# SmartSwitch_i2c_mux.net
KiCad netlist of a schematic drawn in EAGLE
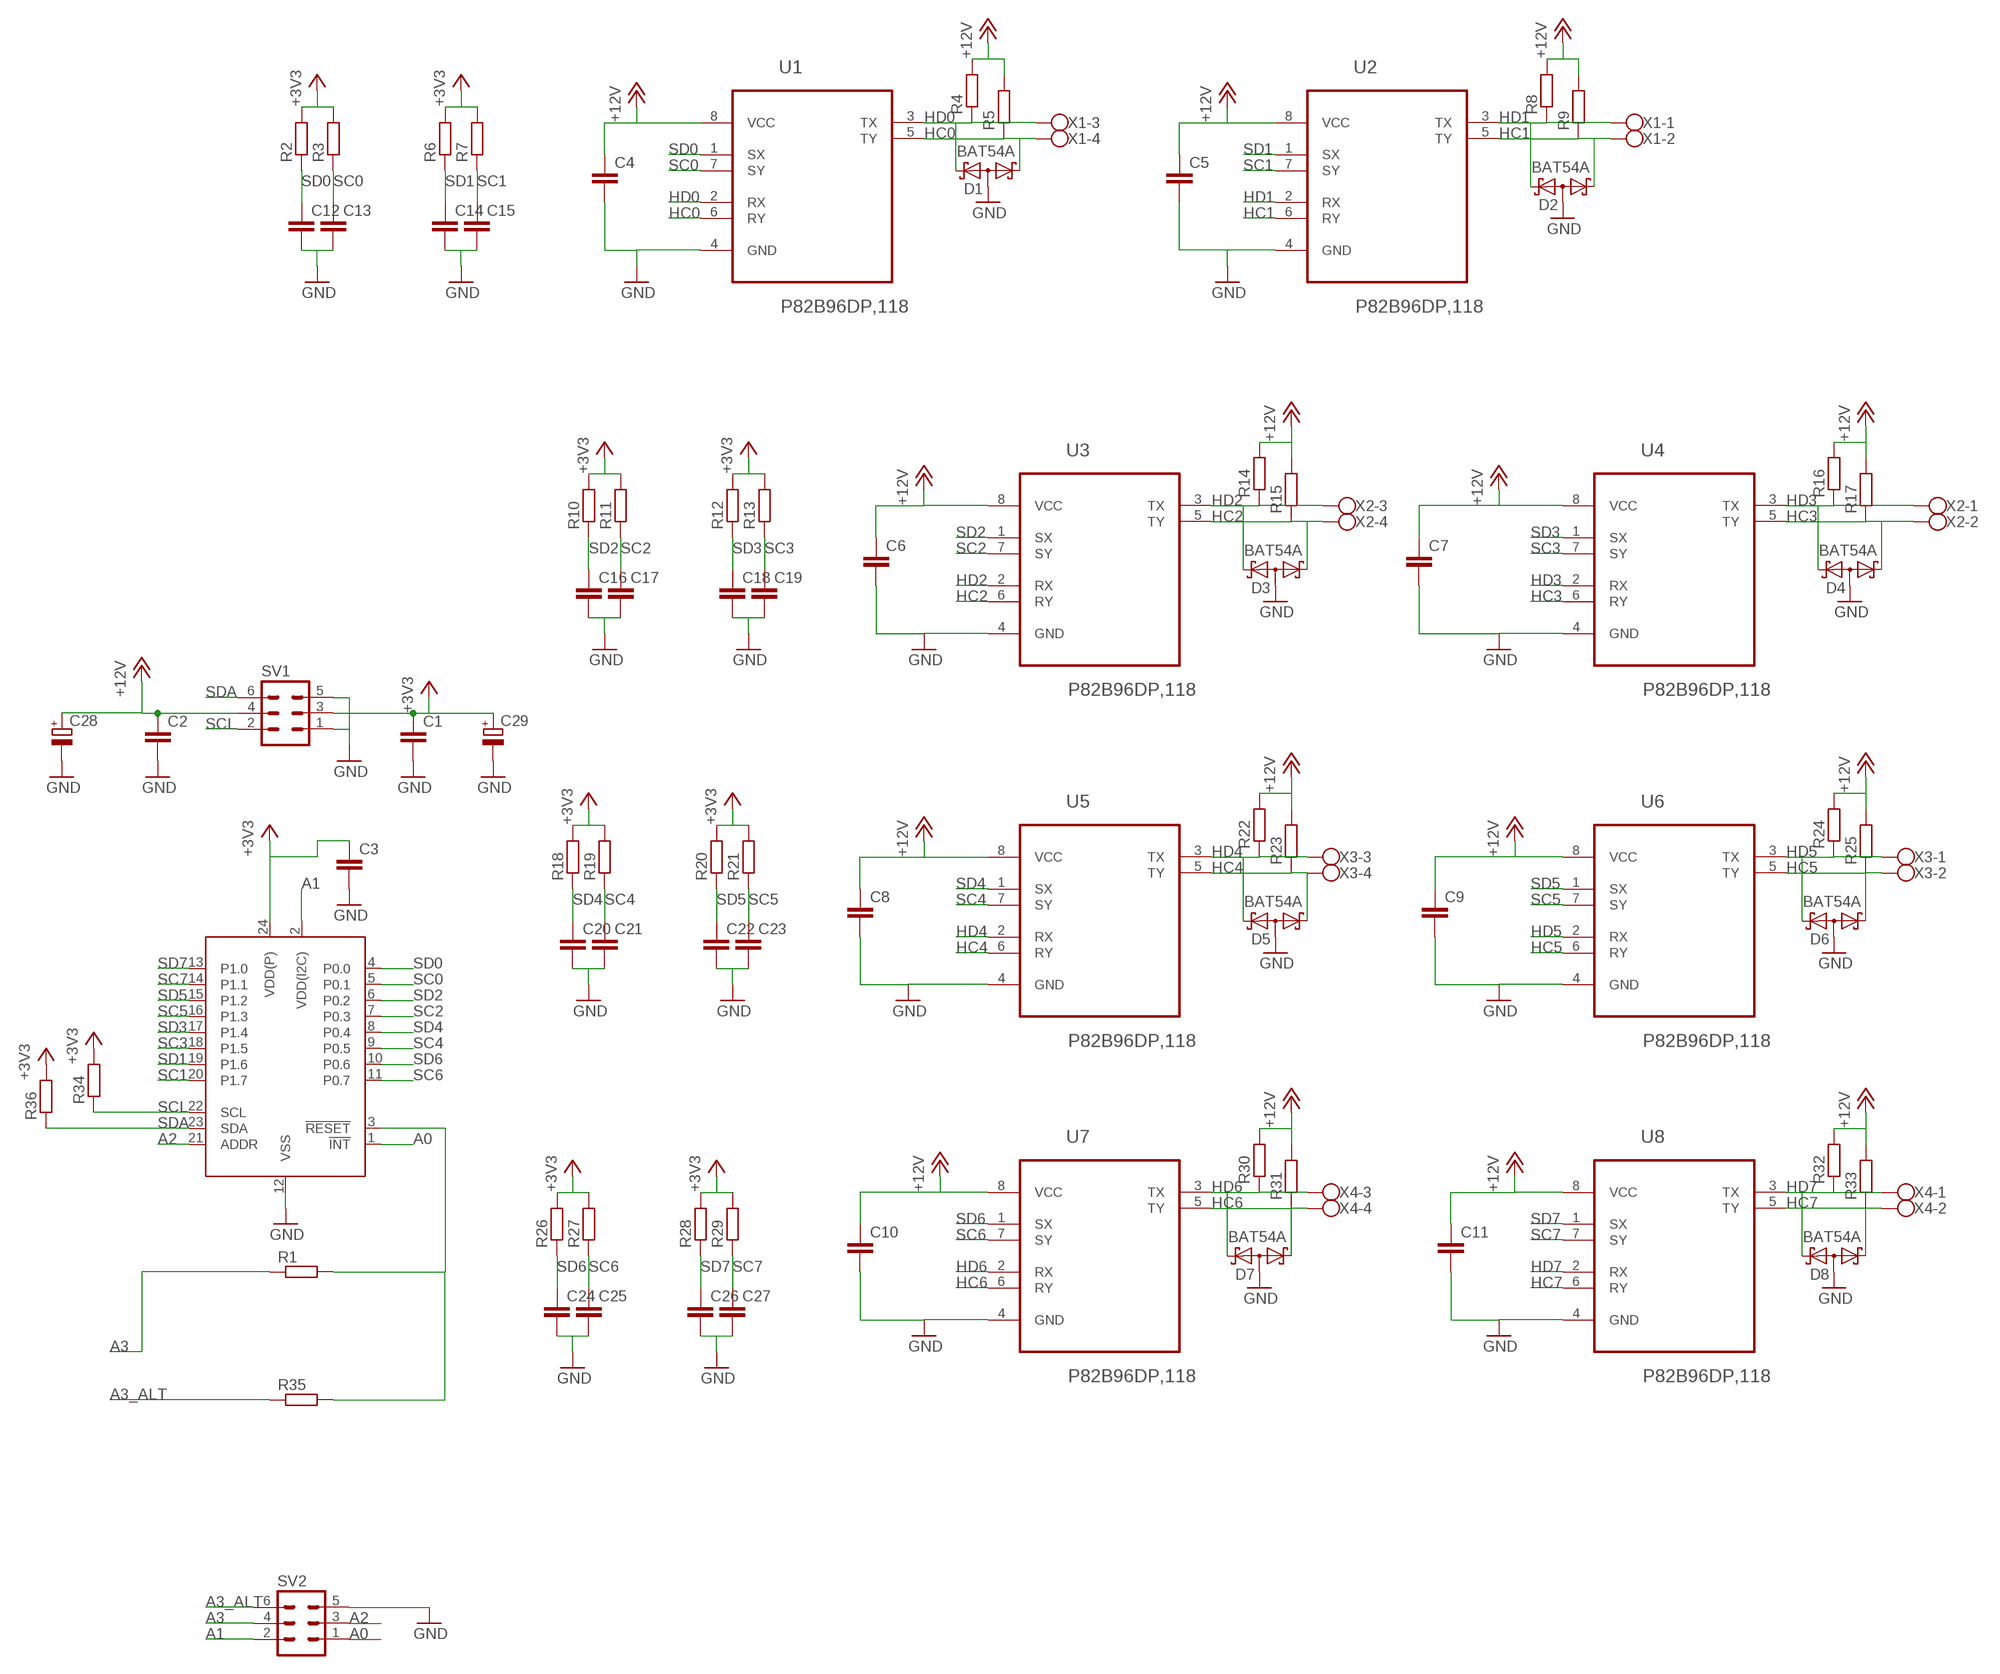
[diagram p0: schematic, sheet 1]

(export (version "E")
  (design (tool "Eeschema 10.0.6"))
  (components
    (comp (ref "C1")
      (value "C-EUC0805K")
      (footprint "eagle-import:C0805K")
      (libsource (lib "eagle-import") (part "C-EUC0805K"))
    )
    (comp (ref "C2")
      (value "C-EUC0805K")
      (footprint "eagle-import:C0805K")
      (libsource (lib "eagle-import") (part "C-EUC0805K"))
    )
    (comp (ref "C3")
      (value "C-EUC0603K")
      (footprint "eagle-import:C0603K")
      (libsource (lib "eagle-import") (part "C-EUC0603K"))
    )
    (comp (ref "C4")
      (value "C-EUC0603K")
      (footprint "eagle-import:C0603K")
      (libsource (lib "eagle-import") (part "C-EUC0603K"))
    )
    (comp (ref "C5")
      (value "C-EUC0603K")
      (footprint "eagle-import:C0603K")
      (libsource (lib "eagle-import") (part "C-EUC0603K"))
    )
    (comp (ref "C6")
      (value "C-EUC0603K")
      (footprint "eagle-import:C0603K")
      (libsource (lib "eagle-import") (part "C-EUC0603K"))
    )
    (comp (ref "C7")
      (value "C-EUC0603K")
      (footprint "eagle-import:C0603K")
      (libsource (lib "eagle-import") (part "C-EUC0603K"))
    )
    (comp (ref "C8")
      (value "C-EUC0603K")
      (footprint "eagle-import:C0603K")
      (libsource (lib "eagle-import") (part "C-EUC0603K"))
    )
    (comp (ref "C9")
      (value "C-EUC0603K")
      (footprint "eagle-import:C0603K")
      (libsource (lib "eagle-import") (part "C-EUC0603K"))
    )
    (comp (ref "C10")
      (value "C-EUC0603K")
      (footprint "eagle-import:C0603K")
      (libsource (lib "eagle-import") (part "C-EUC0603K"))
    )
    (comp (ref "C11")
      (value "C-EUC0603K")
      (footprint "eagle-import:C0603K")
      (libsource (lib "eagle-import") (part "C-EUC0603K"))
    )
    (comp (ref "C12")
      (value "C-EUC0402")
      (footprint "eagle-import:C0402")
      (libsource (lib "eagle-import") (part "C-EUC0402"))
    )
    (comp (ref "C13")
      (value "C-EUC0402")
      (footprint "eagle-import:C0402")
      (libsource (lib "eagle-import") (part "C-EUC0402"))
    )
    (comp (ref "C14")
      (value "C-EUC0402")
      (footprint "eagle-import:C0402")
      (libsource (lib "eagle-import") (part "C-EUC0402"))
    )
    (comp (ref "C15")
      (value "C-EUC0402")
      (footprint "eagle-import:C0402")
      (libsource (lib "eagle-import") (part "C-EUC0402"))
    )
    (comp (ref "C16")
      (value "C-EUC0402")
      (footprint "eagle-import:C0402")
      (libsource (lib "eagle-import") (part "C-EUC0402"))
    )
    (comp (ref "C17")
      (value "C-EUC0402")
      (footprint "eagle-import:C0402")
      (libsource (lib "eagle-import") (part "C-EUC0402"))
    )
    (comp (ref "C18")
      (value "C-EUC0402")
      (footprint "eagle-import:C0402")
      (libsource (lib "eagle-import") (part "C-EUC0402"))
    )
    (comp (ref "C19")
      (value "C-EUC0402")
      (footprint "eagle-import:C0402")
      (libsource (lib "eagle-import") (part "C-EUC0402"))
    )
    (comp (ref "C20")
      (value "C-EUC0402")
      (footprint "eagle-import:C0402")
      (libsource (lib "eagle-import") (part "C-EUC0402"))
    )
    (comp (ref "C21")
      (value "C-EUC0402")
      (footprint "eagle-import:C0402")
      (libsource (lib "eagle-import") (part "C-EUC0402"))
    )
    (comp (ref "C22")
      (value "C-EUC0402")
      (footprint "eagle-import:C0402")
      (libsource (lib "eagle-import") (part "C-EUC0402"))
    )
    (comp (ref "C23")
      (value "C-EUC0402")
      (footprint "eagle-import:C0402")
      (libsource (lib "eagle-import") (part "C-EUC0402"))
    )
    (comp (ref "C24")
      (value "C-EUC0402")
      (footprint "eagle-import:C0402")
      (libsource (lib "eagle-import") (part "C-EUC0402"))
    )
    (comp (ref "C25")
      (value "C-EUC0402")
      (footprint "eagle-import:C0402")
      (libsource (lib "eagle-import") (part "C-EUC0402"))
    )
    (comp (ref "C26")
      (value "C-EUC0402")
      (footprint "eagle-import:C0402")
      (libsource (lib "eagle-import") (part "C-EUC0402"))
    )
    (comp (ref "C27")
      (value "C-EUC0402")
      (footprint "eagle-import:C0402")
      (libsource (lib "eagle-import") (part "C-EUC0402"))
    )
    (comp (ref "C28")
      (value "CPOL-EUUD-6,3X7,7")
      (footprint "eagle-import:UD-6,3X7,7_NICHICON")
      (libsource (lib "eagle-import") (part "CPOL-EUUD-6,3X7,7"))
    )
    (comp (ref "C29")
      (value "CPOL-EUUD-6,3X7,7")
      (footprint "eagle-import:UD-6,3X7,7_NICHICON")
      (libsource (lib "eagle-import") (part "CPOL-EUUD-6,3X7,7"))
    )
    (comp (ref "D1")
      (value "BAT54A")
      (footprint "eagle-import:SOT23")
      (libsource (lib "eagle-import") (part "BAT54A"))
    )
    (comp (ref "D2")
      (value "BAT54A")
      (footprint "eagle-import:SOT23")
      (libsource (lib "eagle-import") (part "BAT54A"))
    )
    (comp (ref "D3")
      (value "BAT54A")
      (footprint "eagle-import:SOT23")
      (libsource (lib "eagle-import") (part "BAT54A"))
    )
    (comp (ref "D4")
      (value "BAT54A")
      (footprint "eagle-import:SOT23")
      (libsource (lib "eagle-import") (part "BAT54A"))
    )
    (comp (ref "D5")
      (value "BAT54A")
      (footprint "eagle-import:SOT23")
      (libsource (lib "eagle-import") (part "BAT54A"))
    )
    (comp (ref "D6")
      (value "BAT54A")
      (footprint "eagle-import:SOT23")
      (libsource (lib "eagle-import") (part "BAT54A"))
    )
    (comp (ref "D7")
      (value "BAT54A")
      (footprint "eagle-import:SOT23")
      (libsource (lib "eagle-import") (part "BAT54A"))
    )
    (comp (ref "D8")
      (value "BAT54A")
      (footprint "eagle-import:SOT23")
      (libsource (lib "eagle-import") (part "BAT54A"))
    )
    (comp (ref "R1")
      (value "R-EU_R0402")
      (footprint "eagle-import:R0402")
      (libsource (lib "eagle-import") (part "R-EU_R0402"))
    )
    (comp (ref "R2")
      (value "R-EU_R0603")
      (footprint "eagle-import:R0603")
      (libsource (lib "eagle-import") (part "R-EU_R0603"))
    )
    (comp (ref "R3")
      (value "R-EU_R0603")
      (footprint "eagle-import:R0603")
      (libsource (lib "eagle-import") (part "R-EU_R0603"))
    )
    (comp (ref "R4")
      (value "R-EU_R1206")
      (footprint "eagle-import:R1206")
      (libsource (lib "eagle-import") (part "R-EU_R1206"))
    )
    (comp (ref "R5")
      (value "R-EU_R1206")
      (footprint "eagle-import:R1206")
      (libsource (lib "eagle-import") (part "R-EU_R1206"))
    )
    (comp (ref "R6")
      (value "R-EU_R0603")
      (footprint "eagle-import:R0603")
      (libsource (lib "eagle-import") (part "R-EU_R0603"))
    )
    (comp (ref "R7")
      (value "R-EU_R0603")
      (footprint "eagle-import:R0603")
      (libsource (lib "eagle-import") (part "R-EU_R0603"))
    )
    (comp (ref "R8")
      (value "R-EU_R1206")
      (footprint "eagle-import:R1206")
      (libsource (lib "eagle-import") (part "R-EU_R1206"))
    )
    (comp (ref "R9")
      (value "R-EU_R1206")
      (footprint "eagle-import:R1206")
      (libsource (lib "eagle-import") (part "R-EU_R1206"))
    )
    (comp (ref "R10")
      (value "R-EU_R0603")
      (footprint "eagle-import:R0603")
      (libsource (lib "eagle-import") (part "R-EU_R0603"))
    )
    (comp (ref "R11")
      (value "R-EU_R0603")
      (footprint "eagle-import:R0603")
      (libsource (lib "eagle-import") (part "R-EU_R0603"))
    )
    (comp (ref "R12")
      (value "R-EU_R0603")
      (footprint "eagle-import:R0603")
      (libsource (lib "eagle-import") (part "R-EU_R0603"))
    )
    (comp (ref "R13")
      (value "R-EU_R0603")
      (footprint "eagle-import:R0603")
      (libsource (lib "eagle-import") (part "R-EU_R0603"))
    )
    (comp (ref "R14")
      (value "R-EU_R1206")
      (footprint "eagle-import:R1206")
      (libsource (lib "eagle-import") (part "R-EU_R1206"))
    )
    (comp (ref "R15")
      (value "R-EU_R1206")
      (footprint "eagle-import:R1206")
      (libsource (lib "eagle-import") (part "R-EU_R1206"))
    )
    (comp (ref "R16")
      (value "R-EU_R1206")
      (footprint "eagle-import:R1206")
      (libsource (lib "eagle-import") (part "R-EU_R1206"))
    )
    (comp (ref "R17")
      (value "R-EU_R1206")
      (footprint "eagle-import:R1206")
      (libsource (lib "eagle-import") (part "R-EU_R1206"))
    )
    (comp (ref "R18")
      (value "R-EU_R0603")
      (footprint "eagle-import:R0603")
      (libsource (lib "eagle-import") (part "R-EU_R0603"))
    )
    (comp (ref "R19")
      (value "R-EU_R0603")
      (footprint "eagle-import:R0603")
      (libsource (lib "eagle-import") (part "R-EU_R0603"))
    )
    (comp (ref "R20")
      (value "R-EU_R0603")
      (footprint "eagle-import:R0603")
      (libsource (lib "eagle-import") (part "R-EU_R0603"))
    )
    (comp (ref "R21")
      (value "R-EU_R0603")
      (footprint "eagle-import:R0603")
      (libsource (lib "eagle-import") (part "R-EU_R0603"))
    )
    (comp (ref "R22")
      (value "R-EU_R1206")
      (footprint "eagle-import:R1206")
      (libsource (lib "eagle-import") (part "R-EU_R1206"))
    )
    (comp (ref "R23")
      (value "R-EU_R1206")
      (footprint "eagle-import:R1206")
      (libsource (lib "eagle-import") (part "R-EU_R1206"))
    )
    (comp (ref "R24")
      (value "R-EU_R1206")
      (footprint "eagle-import:R1206")
      (libsource (lib "eagle-import") (part "R-EU_R1206"))
    )
    (comp (ref "R25")
      (value "R-EU_R1206")
      (footprint "eagle-import:R1206")
      (libsource (lib "eagle-import") (part "R-EU_R1206"))
    )
    (comp (ref "R26")
      (value "R-EU_R0603")
      (footprint "eagle-import:R0603")
      (libsource (lib "eagle-import") (part "R-EU_R0603"))
    )
    (comp (ref "R27")
      (value "R-EU_R0603")
      (footprint "eagle-import:R0603")
      (libsource (lib "eagle-import") (part "R-EU_R0603"))
    )
    (comp (ref "R28")
      (value "R-EU_R0603")
      (footprint "eagle-import:R0603")
      (libsource (lib "eagle-import") (part "R-EU_R0603"))
    )
    (comp (ref "R29")
      (value "R-EU_R0603")
      (footprint "eagle-import:R0603")
      (libsource (lib "eagle-import") (part "R-EU_R0603"))
    )
    (comp (ref "R30")
      (value "R-EU_R1206")
      (footprint "eagle-import:R1206")
      (libsource (lib "eagle-import") (part "R-EU_R1206"))
    )
    (comp (ref "R31")
      (value "R-EU_R1206")
      (footprint "eagle-import:R1206")
      (libsource (lib "eagle-import") (part "R-EU_R1206"))
    )
    (comp (ref "R32")
      (value "R-EU_R1206")
      (footprint "eagle-import:R1206")
      (libsource (lib "eagle-import") (part "R-EU_R1206"))
    )
    (comp (ref "R33")
      (value "R-EU_R1206")
      (footprint "eagle-import:R1206")
      (libsource (lib "eagle-import") (part "R-EU_R1206"))
    )
    (comp (ref "R34")
      (value "R-EU_R0603")
      (footprint "eagle-import:R0603")
      (libsource (lib "eagle-import") (part "R-EU_R0603"))
    )
    (comp (ref "R35")
      (value "R-EU_R0402")
      (footprint "eagle-import:R0402")
      (libsource (lib "eagle-import") (part "R-EU_R0402"))
    )
    (comp (ref "R36")
      (value "R-EU_R0603")
      (footprint "eagle-import:R0603")
      (libsource (lib "eagle-import") (part "R-EU_R0603"))
    )
    (comp (ref "SV1")
      (value "MA03-2")
      (footprint "eagle-import:MA03-2")
      (libsource (lib "eagle-import") (part "MA03-2"))
    )
    (comp (ref "SV2")
      (value "MA03-2")
      (footprint "eagle-import:MA03-2")
      (libsource (lib "eagle-import") (part "MA03-2"))
    )
    (comp (ref "U1")
      (value "P82B96DP,118")
      (footprint "eagle-import:SOP65P490X110-8N")
      (libsource (lib "eagle-import") (part "P82B96DP,118"))
    )
    (comp (ref "U2")
      (value "P82B96DP,118")
      (footprint "eagle-import:SOP65P490X110-8N")
      (libsource (lib "eagle-import") (part "P82B96DP,118"))
    )
    (comp (ref "U3")
      (value "P82B96DP,118")
      (footprint "eagle-import:SOP65P490X110-8N")
      (libsource (lib "eagle-import") (part "P82B96DP,118"))
    )
    (comp (ref "U4")
      (value "P82B96DP,118")
      (footprint "eagle-import:SOP65P490X110-8N")
      (libsource (lib "eagle-import") (part "P82B96DP,118"))
    )
    (comp (ref "U5")
      (value "P82B96DP,118")
      (footprint "eagle-import:SOP65P490X110-8N")
      (libsource (lib "eagle-import") (part "P82B96DP,118"))
    )
    (comp (ref "U6")
      (value "P82B96DP,118")
      (footprint "eagle-import:SOP65P490X110-8N")
      (libsource (lib "eagle-import") (part "P82B96DP,118"))
    )
    (comp (ref "U7")
      (value "P82B96DP,118")
      (footprint "eagle-import:SOP65P490X110-8N")
      (libsource (lib "eagle-import") (part "P82B96DP,118"))
    )
    (comp (ref "U8")
      (value "P82B96DP,118")
      (footprint "eagle-import:SOP65P490X110-8N")
      (libsource (lib "eagle-import") (part "P82B96DP,118"))
    )
    (comp (ref "U10")
      (value "PCAL6416APW")
      (footprint "eagle-import:SOT355-1")
      (libsource (lib "eagle-import") (part "PCAL6416APW"))
    )
    (comp (ref "X1")
      (value "W237-4")
      (footprint "eagle-import:W237-4")
      (libsource (lib "eagle-import") (part "W237-4"))
    )
    (comp (ref "X2")
      (value "W237-4")
      (footprint "eagle-import:W237-4")
      (libsource (lib "eagle-import") (part "W237-4"))
    )
    (comp (ref "X3")
      (value "W237-4")
      (footprint "eagle-import:W237-4")
      (libsource (lib "eagle-import") (part "W237-4"))
    )
    (comp (ref "X4")
      (value "W237-4")
      (footprint "eagle-import:W237-4")
      (libsource (lib "eagle-import") (part "W237-4"))
    )
  )
  (nets
    (net (code "1") (name "+3V3") (class "Default")
      (node (ref "C1") (pin "1") (pinfunction "1_1") (pintype "passive"))
      (node (ref "C29") (pin "+") (pinfunction "+_+") (pintype "passive"))
      (node (ref "C3") (pin "1") (pinfunction "1_1") (pintype "passive"))
      (node (ref "R10") (pin "2") (pinfunction "2_2") (pintype "passive"))
      (node (ref "R11") (pin "2") (pinfunction "2_2") (pintype "passive"))
      (node (ref "R12") (pin "2") (pinfunction "2_2") (pintype "passive"))
      (node (ref "R13") (pin "2") (pinfunction "2_2") (pintype "passive"))
      (node (ref "R18") (pin "2") (pinfunction "2_2") (pintype "passive"))
      (node (ref "R19") (pin "2") (pinfunction "2_2") (pintype "passive"))
      (node (ref "R2") (pin "2") (pinfunction "2_2") (pintype "passive"))
      (node (ref "R20") (pin "2") (pinfunction "2_2") (pintype "passive"))
      (node (ref "R21") (pin "2") (pinfunction "2_2") (pintype "passive"))
      (node (ref "R26") (pin "2") (pinfunction "2_2") (pintype "passive"))
      (node (ref "R27") (pin "2") (pinfunction "2_2") (pintype "passive"))
      (node (ref "R28") (pin "2") (pinfunction "2_2") (pintype "passive"))
      (node (ref "R29") (pin "2") (pinfunction "2_2") (pintype "passive"))
      (node (ref "R3") (pin "2") (pinfunction "2_2") (pintype "passive"))
      (node (ref "R34") (pin "2") (pinfunction "2_2") (pintype "passive"))
      (node (ref "R36") (pin "2") (pinfunction "2_2") (pintype "passive"))
      (node (ref "R6") (pin "2") (pinfunction "2_2") (pintype "passive"))
      (node (ref "R7") (pin "2") (pinfunction "2_2") (pintype "passive"))
      (node (ref "SV1") (pin "3") (pinfunction "3_3") (pintype "passive"))
      (node (ref "U10") (pin "24") (pinfunction "VDD(P)_24") (pintype "power_in"))
    )
    (net (code "2") (name "+12V") (class "Default")
      (node (ref "C10") (pin "1") (pinfunction "1_1") (pintype "passive"))
      (node (ref "C11") (pin "1") (pinfunction "1_1") (pintype "passive"))
      (node (ref "C2") (pin "1") (pinfunction "1_1") (pintype "passive"))
      (node (ref "C28") (pin "+") (pinfunction "+_+") (pintype "passive"))
      (node (ref "C4") (pin "1") (pinfunction "1_1") (pintype "passive"))
      (node (ref "C5") (pin "1") (pinfunction "1_1") (pintype "passive"))
      (node (ref "C6") (pin "1") (pinfunction "1_1") (pintype "passive"))
      (node (ref "C7") (pin "1") (pinfunction "1_1") (pintype "passive"))
      (node (ref "C8") (pin "1") (pinfunction "1_1") (pintype "passive"))
      (node (ref "C9") (pin "1") (pinfunction "1_1") (pintype "passive"))
      (node (ref "R14") (pin "2") (pinfunction "2_2") (pintype "passive"))
      (node (ref "R15") (pin "2") (pinfunction "2_2") (pintype "passive"))
      (node (ref "R16") (pin "2") (pinfunction "2_2") (pintype "passive"))
      (node (ref "R17") (pin "2") (pinfunction "2_2") (pintype "passive"))
      (node (ref "R22") (pin "2") (pinfunction "2_2") (pintype "passive"))
      (node (ref "R23") (pin "2") (pinfunction "2_2") (pintype "passive"))
      (node (ref "R24") (pin "2") (pinfunction "2_2") (pintype "passive"))
      (node (ref "R25") (pin "2") (pinfunction "2_2") (pintype "passive"))
      (node (ref "R30") (pin "2") (pinfunction "2_2") (pintype "passive"))
      (node (ref "R31") (pin "2") (pinfunction "2_2") (pintype "passive"))
      (node (ref "R32") (pin "2") (pinfunction "2_2") (pintype "passive"))
      (node (ref "R33") (pin "2") (pinfunction "2_2") (pintype "passive"))
      (node (ref "R4") (pin "2") (pinfunction "2_2") (pintype "passive"))
      (node (ref "R5") (pin "2") (pinfunction "2_2") (pintype "passive"))
      (node (ref "R8") (pin "2") (pinfunction "2_2") (pintype "passive"))
      (node (ref "R9") (pin "2") (pinfunction "2_2") (pintype "passive"))
      (node (ref "SV1") (pin "4") (pinfunction "4_4") (pintype "passive"))
      (node (ref "U1") (pin "8") (pinfunction "VCC_8") (pintype "power_in"))
      (node (ref "U2") (pin "8") (pinfunction "VCC_8") (pintype "power_in"))
      (node (ref "U3") (pin "8") (pinfunction "VCC_8") (pintype "power_in"))
      (node (ref "U4") (pin "8") (pinfunction "VCC_8") (pintype "power_in"))
      (node (ref "U5") (pin "8") (pinfunction "VCC_8") (pintype "power_in"))
      (node (ref "U6") (pin "8") (pinfunction "VCC_8") (pintype "power_in"))
      (node (ref "U7") (pin "8") (pinfunction "VCC_8") (pintype "power_in"))
      (node (ref "U8") (pin "8") (pinfunction "VCC_8") (pintype "power_in"))
    )
    (net (code "3") (name "/A0") (class "Default")
      (node (ref "SV2") (pin "1") (pinfunction "1_1") (pintype "passive"))
      (node (ref "U10") (pin "1") (pinfunction "~{INT}_1") (pintype "output"))
    )
    (net (code "4") (name "/A1") (class "Default")
      (node (ref "SV2") (pin "2") (pinfunction "2_2") (pintype "passive"))
      (node (ref "U10") (pin "2") (pinfunction "VDD(I2C)_2") (pintype "power_in"))
    )
    (net (code "5") (name "/A2") (class "Default")
      (node (ref "SV2") (pin "3") (pinfunction "3_3") (pintype "passive"))
      (node (ref "U10") (pin "21") (pinfunction "ADDR_21") (pintype "input"))
    )
    (net (code "6") (name "/A3") (class "Default")
      (node (ref "R1") (pin "1") (pinfunction "1_1") (pintype "passive"))
      (node (ref "SV2") (pin "4") (pinfunction "4_4") (pintype "passive"))
    )
    (net (code "7") (name "/A3_ALT") (class "Default")
      (node (ref "R35") (pin "1") (pinfunction "1_1") (pintype "passive"))
      (node (ref "SV2") (pin "6") (pinfunction "6_6") (pintype "passive"))
    )
    (net (code "8") (name "/HC0") (class "Default")
      (node (ref "D1") (pin "1") (pinfunction "K1_1") (pintype "passive"))
      (node (ref "R5") (pin "1") (pinfunction "1_1") (pintype "passive"))
      (node (ref "U1") (pin "5") (pinfunction "TY_5") (pintype "output"))
      (node (ref "U1") (pin "6") (pinfunction "RY_6") (pintype "input"))
      (node (ref "X1") (pin "4") (pinfunction "KL_4") (pintype "passive"))
    )
    (net (code "9") (name "/HC1") (class "Default")
      (node (ref "D2") (pin "1") (pinfunction "K1_1") (pintype "passive"))
      (node (ref "R9") (pin "1") (pinfunction "1_1") (pintype "passive"))
      (node (ref "U2") (pin "5") (pinfunction "TY_5") (pintype "output"))
      (node (ref "U2") (pin "6") (pinfunction "RY_6") (pintype "input"))
      (node (ref "X1") (pin "2") (pinfunction "KL_2") (pintype "passive"))
    )
    (net (code "10") (name "/HC2") (class "Default")
      (node (ref "D3") (pin "1") (pinfunction "K1_1") (pintype "passive"))
      (node (ref "R15") (pin "1") (pinfunction "1_1") (pintype "passive"))
      (node (ref "U3") (pin "5") (pinfunction "TY_5") (pintype "output"))
      (node (ref "U3") (pin "6") (pinfunction "RY_6") (pintype "input"))
      (node (ref "X2") (pin "4") (pinfunction "KL_4") (pintype "passive"))
    )
    (net (code "11") (name "/HC3") (class "Default")
      (node (ref "D4") (pin "1") (pinfunction "K1_1") (pintype "passive"))
      (node (ref "R17") (pin "1") (pinfunction "1_1") (pintype "passive"))
      (node (ref "U4") (pin "5") (pinfunction "TY_5") (pintype "output"))
      (node (ref "U4") (pin "6") (pinfunction "RY_6") (pintype "input"))
      (node (ref "X2") (pin "2") (pinfunction "KL_2") (pintype "passive"))
    )
    (net (code "12") (name "/HC4") (class "Default")
      (node (ref "D5") (pin "1") (pinfunction "K1_1") (pintype "passive"))
      (node (ref "R23") (pin "1") (pinfunction "1_1") (pintype "passive"))
      (node (ref "U5") (pin "5") (pinfunction "TY_5") (pintype "output"))
      (node (ref "U5") (pin "6") (pinfunction "RY_6") (pintype "input"))
      (node (ref "X3") (pin "4") (pinfunction "KL_4") (pintype "passive"))
    )
    (net (code "13") (name "/HC5") (class "Default")
      (node (ref "D6") (pin "1") (pinfunction "K1_1") (pintype "passive"))
      (node (ref "R25") (pin "1") (pinfunction "1_1") (pintype "passive"))
      (node (ref "U6") (pin "5") (pinfunction "TY_5") (pintype "output"))
      (node (ref "U6") (pin "6") (pinfunction "RY_6") (pintype "input"))
      (node (ref "X3") (pin "2") (pinfunction "KL_2") (pintype "passive"))
    )
    (net (code "14") (name "/HC6") (class "Default")
      (node (ref "D7") (pin "1") (pinfunction "K1_1") (pintype "passive"))
      (node (ref "R31") (pin "1") (pinfunction "1_1") (pintype "passive"))
      (node (ref "U7") (pin "5") (pinfunction "TY_5") (pintype "output"))
      (node (ref "U7") (pin "6") (pinfunction "RY_6") (pintype "input"))
      (node (ref "X4") (pin "4") (pinfunction "KL_4") (pintype "passive"))
    )
    (net (code "15") (name "/HC7") (class "Default")
      (node (ref "D8") (pin "1") (pinfunction "K1_1") (pintype "passive"))
      (node (ref "R33") (pin "1") (pinfunction "1_1") (pintype "passive"))
      (node (ref "U8") (pin "5") (pinfunction "TY_5") (pintype "output"))
      (node (ref "U8") (pin "6") (pinfunction "RY_6") (pintype "input"))
      (node (ref "X4") (pin "2") (pinfunction "KL_2") (pintype "passive"))
    )
    (net (code "16") (name "/HD0") (class "Default")
      (node (ref "D1") (pin "2") (pinfunction "K2_2") (pintype "passive"))
      (node (ref "R4") (pin "1") (pinfunction "1_1") (pintype "passive"))
      (node (ref "U1") (pin "2") (pinfunction "RX_2") (pintype "input"))
      (node (ref "U1") (pin "3") (pinfunction "TX_3") (pintype "output"))
      (node (ref "X1") (pin "3") (pinfunction "KL_3") (pintype "passive"))
    )
    (net (code "17") (name "/HD1") (class "Default")
      (node (ref "D2") (pin "2") (pinfunction "K2_2") (pintype "passive"))
      (node (ref "R8") (pin "1") (pinfunction "1_1") (pintype "passive"))
      (node (ref "U2") (pin "2") (pinfunction "RX_2") (pintype "input"))
      (node (ref "U2") (pin "3") (pinfunction "TX_3") (pintype "output"))
      (node (ref "X1") (pin "1") (pinfunction "KL_1") (pintype "passive"))
    )
    (net (code "18") (name "/HD2") (class "Default")
      (node (ref "D3") (pin "2") (pinfunction "K2_2") (pintype "passive"))
      (node (ref "R14") (pin "1") (pinfunction "1_1") (pintype "passive"))
      (node (ref "U3") (pin "2") (pinfunction "RX_2") (pintype "input"))
      (node (ref "U3") (pin "3") (pinfunction "TX_3") (pintype "output"))
      (node (ref "X2") (pin "3") (pinfunction "KL_3") (pintype "passive"))
    )
    (net (code "19") (name "/HD3") (class "Default")
      (node (ref "D4") (pin "2") (pinfunction "K2_2") (pintype "passive"))
      (node (ref "R16") (pin "1") (pinfunction "1_1") (pintype "passive"))
      (node (ref "U4") (pin "2") (pinfunction "RX_2") (pintype "input"))
      (node (ref "U4") (pin "3") (pinfunction "TX_3") (pintype "output"))
      (node (ref "X2") (pin "1") (pinfunction "KL_1") (pintype "passive"))
    )
    (net (code "20") (name "/HD4") (class "Default")
      (node (ref "D5") (pin "2") (pinfunction "K2_2") (pintype "passive"))
      (node (ref "R22") (pin "1") (pinfunction "1_1") (pintype "passive"))
      (node (ref "U5") (pin "2") (pinfunction "RX_2") (pintype "input"))
      (node (ref "U5") (pin "3") (pinfunction "TX_3") (pintype "output"))
      (node (ref "X3") (pin "3") (pinfunction "KL_3") (pintype "passive"))
    )
    (net (code "21") (name "/HD5") (class "Default")
      (node (ref "D6") (pin "2") (pinfunction "K2_2") (pintype "passive"))
      (node (ref "R24") (pin "1") (pinfunction "1_1") (pintype "passive"))
      (node (ref "U6") (pin "2") (pinfunction "RX_2") (pintype "input"))
      (node (ref "U6") (pin "3") (pinfunction "TX_3") (pintype "output"))
      (node (ref "X3") (pin "1") (pinfunction "KL_1") (pintype "passive"))
    )
    (net (code "22") (name "/HD6") (class "Default")
      (node (ref "D7") (pin "2") (pinfunction "K2_2") (pintype "passive"))
      (node (ref "R30") (pin "1") (pinfunction "1_1") (pintype "passive"))
      (node (ref "U7") (pin "2") (pinfunction "RX_2") (pintype "input"))
      (node (ref "U7") (pin "3") (pinfunction "TX_3") (pintype "output"))
      (node (ref "X4") (pin "3") (pinfunction "KL_3") (pintype "passive"))
    )
    (net (code "23") (name "/HD7") (class "Default")
      (node (ref "D8") (pin "2") (pinfunction "K2_2") (pintype "passive"))
      (node (ref "R32") (pin "1") (pinfunction "1_1") (pintype "passive"))
      (node (ref "U8") (pin "2") (pinfunction "RX_2") (pintype "input"))
      (node (ref "U8") (pin "3") (pinfunction "TX_3") (pintype "output"))
      (node (ref "X4") (pin "1") (pinfunction "KL_1") (pintype "passive"))
    )
    (net (code "24") (name "/SC0") (class "Default")
      (node (ref "C13") (pin "1") (pinfunction "1_1") (pintype "passive"))
      (node (ref "R3") (pin "1") (pinfunction "1_1") (pintype "passive"))
      (node (ref "U1") (pin "7") (pinfunction "SY_7") (pintype "bidirectional"))
      (node (ref "U10") (pin "5") (pinfunction "P0.1_5") (pintype "bidirectional"))
    )
    (net (code "25") (name "/SC1") (class "Default")
      (node (ref "C15") (pin "1") (pinfunction "1_1") (pintype "passive"))
      (node (ref "R7") (pin "1") (pinfunction "1_1") (pintype "passive"))
      (node (ref "U10") (pin "20") (pinfunction "P1.7_20") (pintype "bidirectional"))
      (node (ref "U2") (pin "7") (pinfunction "SY_7") (pintype "bidirectional"))
    )
    (net (code "26") (name "/SC2") (class "Default")
      (node (ref "C17") (pin "1") (pinfunction "1_1") (pintype "passive"))
      (node (ref "R11") (pin "1") (pinfunction "1_1") (pintype "passive"))
      (node (ref "U10") (pin "7") (pinfunction "P0.3_7") (pintype "bidirectional"))
      (node (ref "U3") (pin "7") (pinfunction "SY_7") (pintype "bidirectional"))
    )
    (net (code "27") (name "/SC3") (class "Default")
      (node (ref "C19") (pin "1") (pinfunction "1_1") (pintype "passive"))
      (node (ref "R13") (pin "1") (pinfunction "1_1") (pintype "passive"))
      (node (ref "U10") (pin "18") (pinfunction "P1.5_18") (pintype "bidirectional"))
      (node (ref "U4") (pin "7") (pinfunction "SY_7") (pintype "bidirectional"))
    )
    (net (code "28") (name "/SC4") (class "Default")
      (node (ref "C21") (pin "1") (pinfunction "1_1") (pintype "passive"))
      (node (ref "R19") (pin "1") (pinfunction "1_1") (pintype "passive"))
      (node (ref "U10") (pin "9") (pinfunction "P0.5_9") (pintype "bidirectional"))
      (node (ref "U5") (pin "7") (pinfunction "SY_7") (pintype "bidirectional"))
    )
    (net (code "29") (name "/SC5") (class "Default")
      (node (ref "C23") (pin "1") (pinfunction "1_1") (pintype "passive"))
      (node (ref "R21") (pin "1") (pinfunction "1_1") (pintype "passive"))
      (node (ref "U10") (pin "16") (pinfunction "P1.3_16") (pintype "bidirectional"))
      (node (ref "U6") (pin "7") (pinfunction "SY_7") (pintype "bidirectional"))
    )
    (net (code "30") (name "/SC6") (class "Default")
      (node (ref "C25") (pin "1") (pinfunction "1_1") (pintype "passive"))
      (node (ref "R27") (pin "1") (pinfunction "1_1") (pintype "passive"))
      (node (ref "U10") (pin "11") (pinfunction "P0.7_11") (pintype "bidirectional"))
      (node (ref "U7") (pin "7") (pinfunction "SY_7") (pintype "bidirectional"))
    )
    (net (code "31") (name "/SC7") (class "Default")
      (node (ref "C27") (pin "1") (pinfunction "1_1") (pintype "passive"))
      (node (ref "R29") (pin "1") (pinfunction "1_1") (pintype "passive"))
      (node (ref "U10") (pin "14") (pinfunction "P1.1_14") (pintype "bidirectional"))
      (node (ref "U8") (pin "7") (pinfunction "SY_7") (pintype "bidirectional"))
    )
    (net (code "32") (name "/SCL") (class "Default")
      (node (ref "R34") (pin "1") (pinfunction "1_1") (pintype "passive"))
      (node (ref "SV1") (pin "2") (pinfunction "2_2") (pintype "passive"))
      (node (ref "U10") (pin "22") (pinfunction "SCL_22") (pintype "bidirectional"))
    )
    (net (code "33") (name "/SD0") (class "Default")
      (node (ref "C12") (pin "1") (pinfunction "1_1") (pintype "passive"))
      (node (ref "R2") (pin "1") (pinfunction "1_1") (pintype "passive"))
      (node (ref "U1") (pin "1") (pinfunction "SX_1") (pintype "bidirectional"))
      (node (ref "U10") (pin "4") (pinfunction "P0.0_4") (pintype "bidirectional"))
    )
    (net (code "34") (name "/SD1") (class "Default")
      (node (ref "C14") (pin "1") (pinfunction "1_1") (pintype "passive"))
      (node (ref "R6") (pin "1") (pinfunction "1_1") (pintype "passive"))
      (node (ref "U10") (pin "19") (pinfunction "P1.6_19") (pintype "bidirectional"))
      (node (ref "U2") (pin "1") (pinfunction "SX_1") (pintype "bidirectional"))
    )
    (net (code "35") (name "/SD2") (class "Default")
      (node (ref "C16") (pin "1") (pinfunction "1_1") (pintype "passive"))
      (node (ref "R10") (pin "1") (pinfunction "1_1") (pintype "passive"))
      (node (ref "U10") (pin "6") (pinfunction "P0.2_6") (pintype "bidirectional"))
      (node (ref "U3") (pin "1") (pinfunction "SX_1") (pintype "bidirectional"))
    )
    (net (code "36") (name "/SD3") (class "Default")
      (node (ref "C18") (pin "1") (pinfunction "1_1") (pintype "passive"))
      (node (ref "R12") (pin "1") (pinfunction "1_1") (pintype "passive"))
      (node (ref "U10") (pin "17") (pinfunction "P1.4_17") (pintype "bidirectional"))
      (node (ref "U4") (pin "1") (pinfunction "SX_1") (pintype "bidirectional"))
    )
    (net (code "37") (name "/SD4") (class "Default")
      (node (ref "C20") (pin "1") (pinfunction "1_1") (pintype "passive"))
      (node (ref "R18") (pin "1") (pinfunction "1_1") (pintype "passive"))
      (node (ref "U10") (pin "8") (pinfunction "P0.4_8") (pintype "bidirectional"))
      (node (ref "U5") (pin "1") (pinfunction "SX_1") (pintype "bidirectional"))
    )
    (net (code "38") (name "/SD5") (class "Default")
      (node (ref "C22") (pin "1") (pinfunction "1_1") (pintype "passive"))
      (node (ref "R20") (pin "1") (pinfunction "1_1") (pintype "passive"))
      (node (ref "U10") (pin "15") (pinfunction "P1.2_15") (pintype "bidirectional"))
      (node (ref "U6") (pin "1") (pinfunction "SX_1") (pintype "bidirectional"))
    )
    (net (code "39") (name "/SD6") (class "Default")
      (node (ref "C24") (pin "1") (pinfunction "1_1") (pintype "passive"))
      (node (ref "R26") (pin "1") (pinfunction "1_1") (pintype "passive"))
      (node (ref "U10") (pin "10") (pinfunction "P0.6_10") (pintype "bidirectional"))
      (node (ref "U7") (pin "1") (pinfunction "SX_1") (pintype "bidirectional"))
    )
    (net (code "40") (name "/SD7") (class "Default")
      (node (ref "C26") (pin "1") (pinfunction "1_1") (pintype "passive"))
      (node (ref "R28") (pin "1") (pinfunction "1_1") (pintype "passive"))
      (node (ref "U10") (pin "13") (pinfunction "P1.0_13") (pintype "bidirectional"))
      (node (ref "U8") (pin "1") (pinfunction "SX_1") (pintype "bidirectional"))
    )
    (net (code "41") (name "/SDA") (class "Default")
      (node (ref "R36") (pin "1") (pinfunction "1_1") (pintype "passive"))
      (node (ref "SV1") (pin "6") (pinfunction "6_6") (pintype "passive"))
      (node (ref "U10") (pin "23") (pinfunction "SDA_23") (pintype "bidirectional"))
    )
    (net (code "42") (name "GND") (class "Default")
      (node (ref "C1") (pin "2") (pinfunction "2_2") (pintype "passive"))
      (node (ref "C10") (pin "2") (pinfunction "2_2") (pintype "passive"))
      (node (ref "C11") (pin "2") (pinfunction "2_2") (pintype "passive"))
      (node (ref "C12") (pin "2") (pinfunction "2_2") (pintype "passive"))
      (node (ref "C13") (pin "2") (pinfunction "2_2") (pintype "passive"))
      (node (ref "C14") (pin "2") (pinfunction "2_2") (pintype "passive"))
      (node (ref "C15") (pin "2") (pinfunction "2_2") (pintype "passive"))
      (node (ref "C16") (pin "2") (pinfunction "2_2") (pintype "passive"))
      (node (ref "C17") (pin "2") (pinfunction "2_2") (pintype "passive"))
      (node (ref "C18") (pin "2") (pinfunction "2_2") (pintype "passive"))
      (node (ref "C19") (pin "2") (pinfunction "2_2") (pintype "passive"))
      (node (ref "C2") (pin "2") (pinfunction "2_2") (pintype "passive"))
      (node (ref "C20") (pin "2") (pinfunction "2_2") (pintype "passive"))
      (node (ref "C21") (pin "2") (pinfunction "2_2") (pintype "passive"))
      (node (ref "C22") (pin "2") (pinfunction "2_2") (pintype "passive"))
      (node (ref "C23") (pin "2") (pinfunction "2_2") (pintype "passive"))
      (node (ref "C24") (pin "2") (pinfunction "2_2") (pintype "passive"))
      (node (ref "C25") (pin "2") (pinfunction "2_2") (pintype "passive"))
      (node (ref "C26") (pin "2") (pinfunction "2_2") (pintype "passive"))
      (node (ref "C27") (pin "2") (pinfunction "2_2") (pintype "passive"))
      (node (ref "C28") (pin "-") (pinfunction "-_-") (pintype "passive"))
      (node (ref "C29") (pin "-") (pinfunction "-_-") (pintype "passive"))
      (node (ref "C3") (pin "2") (pinfunction "2_2") (pintype "passive"))
      (node (ref "C4") (pin "2") (pinfunction "2_2") (pintype "passive"))
      (node (ref "C5") (pin "2") (pinfunction "2_2") (pintype "passive"))
      (node (ref "C6") (pin "2") (pinfunction "2_2") (pintype "passive"))
      (node (ref "C7") (pin "2") (pinfunction "2_2") (pintype "passive"))
      (node (ref "C8") (pin "2") (pinfunction "2_2") (pintype "passive"))
      (node (ref "C9") (pin "2") (pinfunction "2_2") (pintype "passive"))
      (node (ref "D1") (pin "3") (pinfunction "A1A2_3") (pintype "passive"))
      (node (ref "D2") (pin "3") (pinfunction "A1A2_3") (pintype "passive"))
      (node (ref "D3") (pin "3") (pinfunction "A1A2_3") (pintype "passive"))
      (node (ref "D4") (pin "3") (pinfunction "A1A2_3") (pintype "passive"))
      (node (ref "D5") (pin "3") (pinfunction "A1A2_3") (pintype "passive"))
      (node (ref "D6") (pin "3") (pinfunction "A1A2_3") (pintype "passive"))
      (node (ref "D7") (pin "3") (pinfunction "A1A2_3") (pintype "passive"))
      (node (ref "D8") (pin "3") (pinfunction "A1A2_3") (pintype "passive"))
      (node (ref "SV1") (pin "1") (pinfunction "1_1") (pintype "passive"))
      (node (ref "SV1") (pin "5") (pinfunction "5_5") (pintype "passive"))
      (node (ref "SV2") (pin "5") (pinfunction "5_5") (pintype "passive"))
      (node (ref "U1") (pin "4") (pinfunction "GND_4") (pintype "passive"))
      (node (ref "U10") (pin "12") (pinfunction "VSS_12") (pintype "bidirectional"))
      (node (ref "U2") (pin "4") (pinfunction "GND_4") (pintype "passive"))
      (node (ref "U3") (pin "4") (pinfunction "GND_4") (pintype "passive"))
      (node (ref "U4") (pin "4") (pinfunction "GND_4") (pintype "passive"))
      (node (ref "U5") (pin "4") (pinfunction "GND_4") (pintype "passive"))
      (node (ref "U6") (pin "4") (pinfunction "GND_4") (pintype "passive"))
      (node (ref "U7") (pin "4") (pinfunction "GND_4") (pintype "passive"))
      (node (ref "U8") (pin "4") (pinfunction "GND_4") (pintype "passive"))
    )
    (net (code "43") (name "Net-(U10-~{RESET})") (class "Default")
      (node (ref "R1") (pin "2") (pinfunction "2_2") (pintype "passive"))
      (node (ref "R35") (pin "2") (pinfunction "2_2") (pintype "passive"))
      (node (ref "U10") (pin "3") (pinfunction "~{RESET}_3") (pintype "input"))
    )
  )
)
